# xARMtoR.net
KiCad netlist of a schematic drawn in Altium Designer
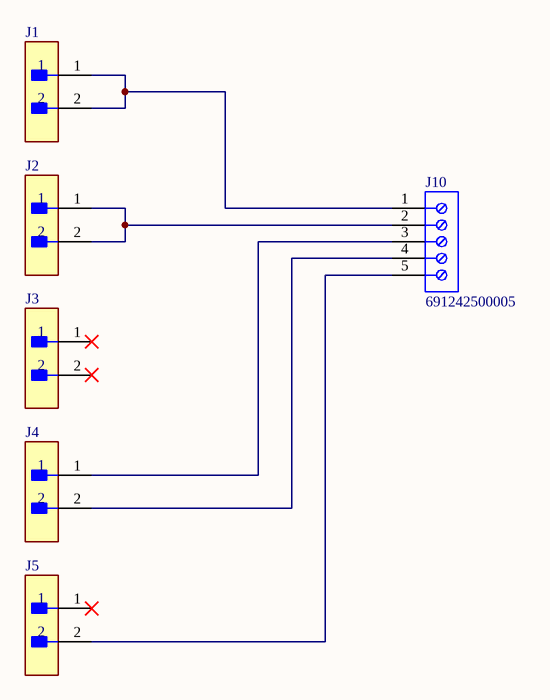
[diagram p0: xARMtoR.SchDoc]

(export (version "E")
  (design (tool "Eeschema 10.0.6"))
  (components
    (comp (ref "J1")
      (value "M50-3530242")
      (footprint "FP-M50-3530242-MFG")
      (description "CONN HEADER VERT 2POS 1.27MM")
      (libsource (lib "Altium Content Vault") (part "3bc925449376181038e59eaffc5286c"))
    )
    (comp (ref "J2")
      (value "M50-3530242")
      (footprint "FP-M50-3530242-MFG")
      (description "CONN HEADER VERT 2POS 1.27MM")
      (libsource (lib "Altium Content Vault") (part "3bc925449376181038e59eaffc5286c"))
    )
    (comp (ref "J3")
      (value "M50-3530242")
      (footprint "FP-M50-3530242-MFG")
      (description "CONN HEADER VERT 2POS 1.27MM")
      (libsource (lib "Altium Content Vault") (part "3bc925449376181038e59eaffc5286c"))
    )
    (comp (ref "J4")
      (value "M50-3530242")
      (footprint "FP-M50-3530242-MFG")
      (description "CONN HEADER VERT 2POS 1.27MM")
      (libsource (lib "Altium Content Vault") (part "3bc925449376181038e59eaffc5286c"))
    )
    (comp (ref "J5")
      (value "M50-3530242")
      (footprint "FP-M50-3530242-MFG")
      (description "CONN HEADER VERT 2POS 1.27MM")
      (libsource (lib "Altium Content Vault") (part "3bc925449376181038e59eaffc5286c"))
    )
    (comp (ref "J10")
      (value "691242500005")
      (footprint "691242500005")
      (description "Terminal Block, 5.08MM Pitch, Vertical, Rising Cage Clamp, 12-30 AWG, 5 Pin")
      (libsource (lib "Altium Content Vault") (part "TBL - 1R - 05P - Screw"))
    )
  )
  (nets
    (net (code "1") (name "Net-(J1-Pad1)") (class "Default")
      (node (ref "J1") (pin "1") (pinfunction "1_1") (pintype "passive"))
      (node (ref "J1") (pin "2") (pinfunction "2_2") (pintype "passive"))
      (node (ref "J10") (pin "1") (pinfunction "1_1") (pintype "passive"))
    )
    (net (code "2") (name "Net-(J10-Pad2)") (class "Default")
      (node (ref "J10") (pin "2") (pinfunction "2_2") (pintype "passive"))
      (node (ref "J2") (pin "1") (pinfunction "1_1") (pintype "passive"))
      (node (ref "J2") (pin "2") (pinfunction "2_2") (pintype "passive"))
    )
    (net (code "3") (name "Net-(J10-Pad3)") (class "Default")
      (node (ref "J10") (pin "3") (pinfunction "3_3") (pintype "passive"))
      (node (ref "J4") (pin "1") (pinfunction "1_1") (pintype "passive"))
    )
    (net (code "4") (name "Net-(J10-Pad4)") (class "Default")
      (node (ref "J10") (pin "4") (pinfunction "4_4") (pintype "passive"))
      (node (ref "J4") (pin "2") (pinfunction "2_2") (pintype "passive"))
    )
    (net (code "5") (name "Net-(J10-Pad5)") (class "Default")
      (node (ref "J10") (pin "5") (pinfunction "5_5") (pintype "passive"))
      (node (ref "J5") (pin "2") (pinfunction "2_2") (pintype "passive"))
    )
    (net (code "6") (name "unconnected-(J3-Pad1)") (class "Default")
      (node (ref "J3") (pin "1") (pinfunction "1_1") (pintype "passive+no_connect"))
    )
    (net (code "7") (name "unconnected-(J3-Pad2)") (class "Default")
      (node (ref "J3") (pin "2") (pinfunction "2_2") (pintype "passive+no_connect"))
    )
    (net (code "8") (name "unconnected-(J5-Pad1)") (class "Default")
      (node (ref "J5") (pin "1") (pinfunction "1_1") (pintype "passive+no_connect"))
    )
  )
)
